# BigLMA.net
KiCad netlist of a schematic drawn in EAGLE
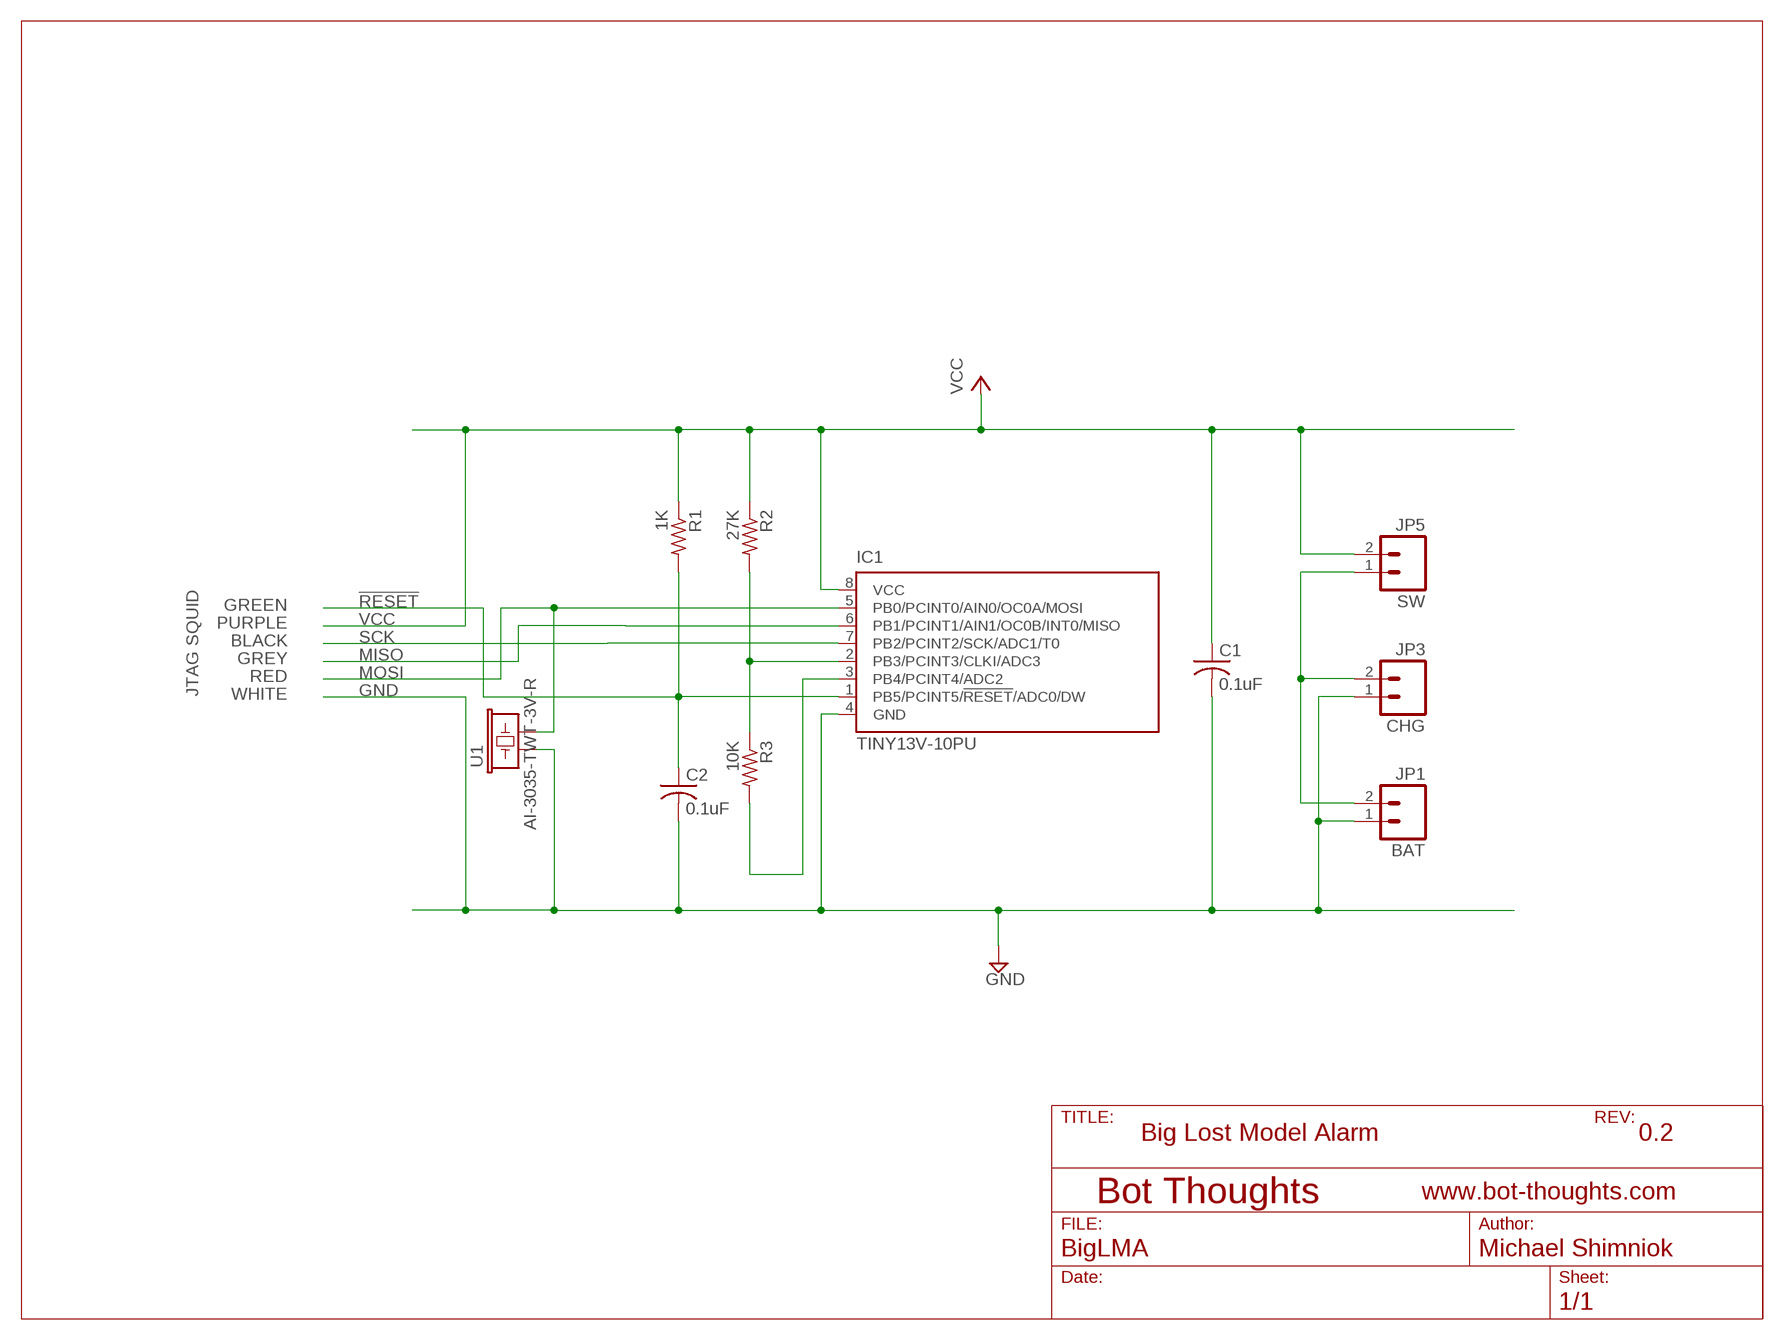
[diagram p0: schematic, sheet 1]

(export (version "E")
  (design (tool "Eeschema 10.0.6"))
  (components
    (comp (ref "C1")
      (value "0.1uF")
      (footprint "eagle-import:C0603")
      (fields (field (name "PARTNO") "GRM188R60J105KA01D"))
      (libsource (lib "eagle-import") (part "C-USC0603"))
    )
    (comp (ref "C2")
      (value "0.1uF")
      (footprint "eagle-import:C0603")
      (fields (field (name "PARTNO") "GRM188R60J105KA01D"))
      (libsource (lib "eagle-import") (part "C-USC0603"))
    )
    (comp (ref "IC1")
      (value "TINY13V-10PU")
      (footprint "eagle-import:DIL08")
      (fields (field (name "MPN") "ATTINY13V-10PU"))
      (libsource (lib "eagle-import") (part "TINY13PUV-10"))
    )
    (comp (ref "JP1")
      (value "BAT")
      (footprint "eagle-import:JST-2-PTH")
      (libsource (lib "eagle-import") (part "M02JST-PTH-2"))
    )
    (comp (ref "JP3")
      (value "CHG")
      (footprint "eagle-import:1X02")
      (libsource (lib "eagle-import") (part "M02PTH"))
    )
    (comp (ref "JP5")
      (value "SW")
      (footprint "eagle-import:1X02")
      (libsource (lib "eagle-import") (part "M02PTH"))
    )
    (comp (ref "R1")
      (value "1K")
      (footprint "eagle-import:R0603")
      (fields (field (name "PARTNO") "ERJ-3GEYJ102V"))
      (libsource (lib "eagle-import") (part "R-US_R0603"))
    )
    (comp (ref "R2")
      (value "27K")
      (footprint "eagle-import:R0603")
      (fields (field (name "PARTNO") "RR0816P-273-D"))
      (libsource (lib "eagle-import") (part "R-US_R0603"))
    )
    (comp (ref "R3")
      (value "10K")
      (footprint "eagle-import:R0603")
      (fields (field (name "PARTNO") "RR0816P-103-D"))
      (libsource (lib "eagle-import") (part "R-US_R0603"))
    )
    (comp (ref "U1")
      (value "AI-3035-TWT-3V-R")
      (footprint "eagle-import:BUZZER-30MM_PTH")
      (libsource (lib "eagle-import") (part "AI-3035-TWT-3V-RPTH"))
    )
  )
  (nets
    (net (code "1") (name "/MISO") (class "Default")
      (node (ref "IC1") (pin "6") (pinfunction "PB1/PCINT1/AIN1/OC0B/INT0/MISO_6") (pintype "bidirectional"))
    )
    (net (code "2") (name "/MOSI") (class "Default")
      (node (ref "IC1") (pin "5") (pinfunction "PB0/PCINT0/AIN0/OC0A/MOSI_5") (pintype "bidirectional"))
      (node (ref "U1") (pin "P$2") (pinfunction "2_P$2") (pintype "passive"))
    )
    (net (code "3") (name "/SCK") (class "Default")
      (node (ref "IC1") (pin "7") (pinfunction "PB2/PCINT2/SCK/ADC1/T0_7") (pintype "bidirectional"))
    )
    (net (code "4") (name "/~{RESET}") (class "Default")
      (node (ref "C2") (pin "1") (pinfunction "1_1") (pintype "passive"))
      (node (ref "IC1") (pin "1") (pinfunction "PB5/PCINT5/~{RESET}/ADC0/DW_1") (pintype "bidirectional"))
      (node (ref "R1") (pin "2") (pinfunction "2_2") (pintype "passive"))
    )
    (net (code "5") (name "GND") (class "Default")
      (node (ref "C1") (pin "2") (pinfunction "2_2") (pintype "passive"))
      (node (ref "C2") (pin "2") (pinfunction "2_2") (pintype "passive"))
      (node (ref "IC1") (pin "4") (pinfunction "GND_4") (pintype "power_in"))
      (node (ref "JP1") (pin "1") (pinfunction "1_1") (pintype "passive"))
      (node (ref "JP3") (pin "1") (pinfunction "1_1") (pintype "passive"))
      (node (ref "U1") (pin "P$1") (pinfunction "1_P$1") (pintype "passive"))
    )
    (net (code "6") (name "Net-(IC1-PB3{slash}PCINT3{slash}CLKI{slash}ADC3)") (class "Default")
      (node (ref "IC1") (pin "2") (pinfunction "PB3/PCINT3/CLKI/ADC3_2") (pintype "bidirectional"))
      (node (ref "R2") (pin "2") (pinfunction "2_2") (pintype "passive"))
      (node (ref "R3") (pin "1") (pinfunction "1_1") (pintype "passive"))
    )
    (net (code "7") (name "Net-(IC1-PB4{slash}PCINT4{slash}ADC2)") (class "Default")
      (node (ref "IC1") (pin "3") (pinfunction "PB4/PCINT4/ADC2_3") (pintype "bidirectional"))
      (node (ref "R3") (pin "2") (pinfunction "2_2") (pintype "passive"))
    )
    (net (code "8") (name "Net-(JP1-Pad2)") (class "Default")
      (node (ref "JP1") (pin "2") (pinfunction "2_2") (pintype "passive"))
      (node (ref "JP3") (pin "2") (pinfunction "2_2") (pintype "passive"))
      (node (ref "JP5") (pin "1") (pinfunction "1_1") (pintype "passive"))
    )
    (net (code "9") (name "VCC") (class "Default")
      (node (ref "C1") (pin "1") (pinfunction "1_1") (pintype "passive"))
      (node (ref "IC1") (pin "8") (pinfunction "VCC_8") (pintype "power_in"))
      (node (ref "JP5") (pin "2") (pinfunction "2_2") (pintype "passive"))
      (node (ref "R1") (pin "1") (pinfunction "1_1") (pintype "passive"))
      (node (ref "R2") (pin "1") (pinfunction "1_1") (pintype "passive"))
    )
  )
)
